# voeding.net
KiCad netlist of a schematic drawn in Altium Designer
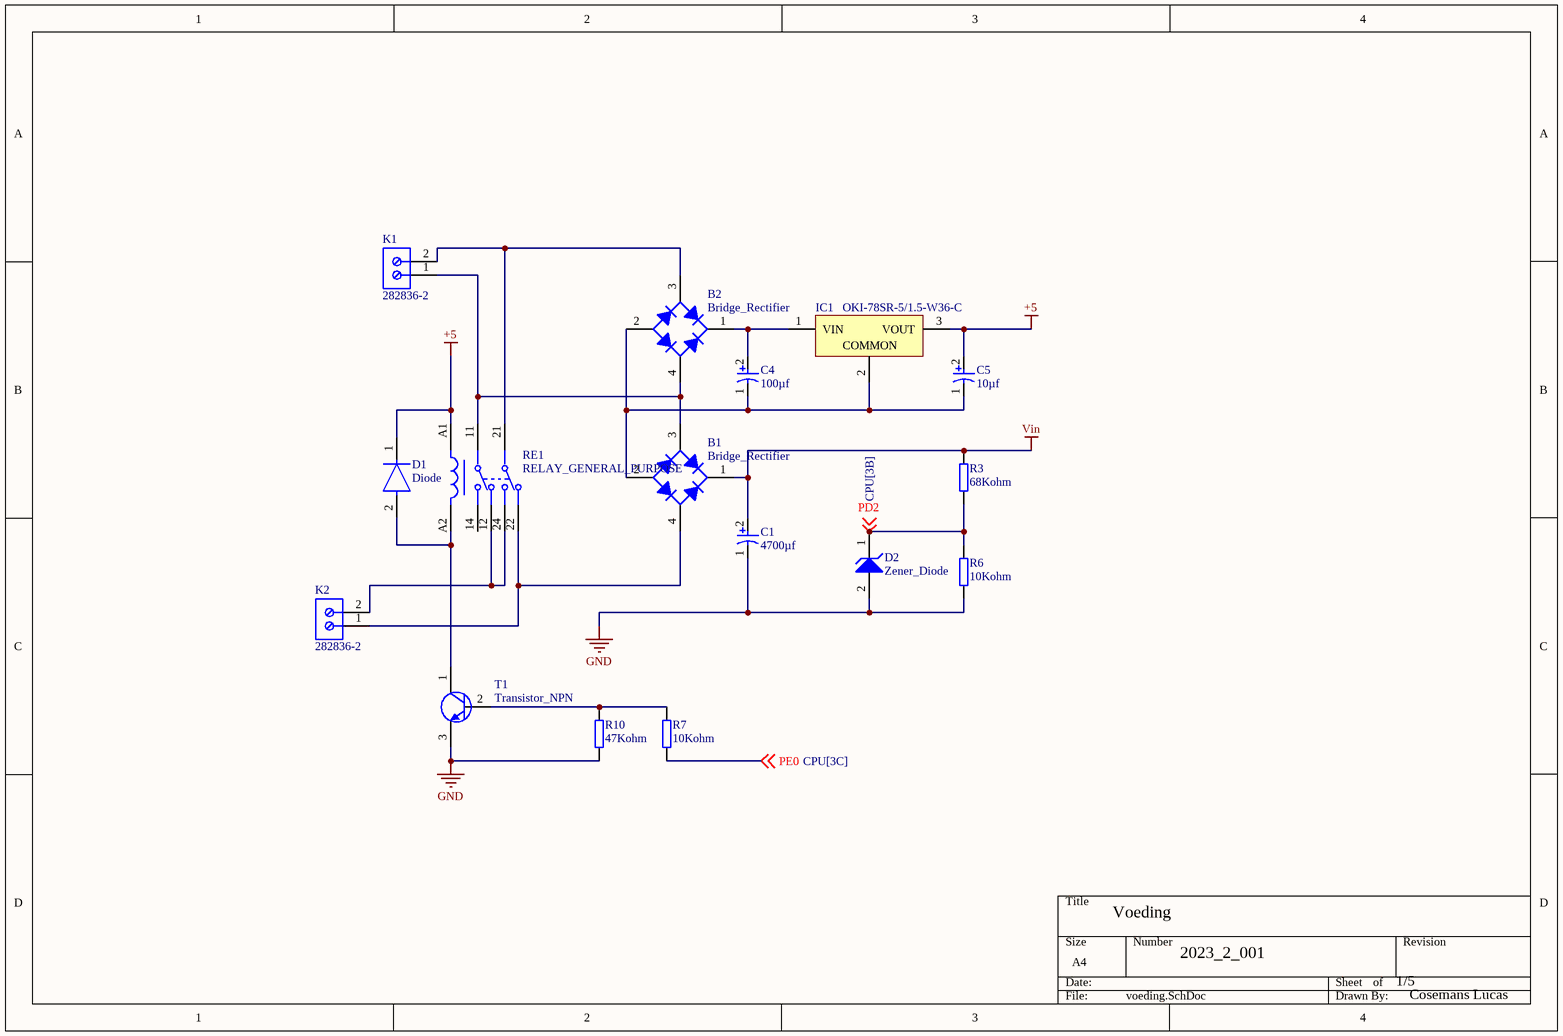
[diagram p0: voeding.SchDoc]

(export (version "E")
  (design (tool "Eeschema 10.0.6"))
  (components
    (comp (ref "B1")
      (value "Bridge_Rectifier")
      (footprint "ttf")
      (fields (field (name "MANUFACTURER") "Diodes Inc"))
      (libsource (lib "Schematic_soldeerstation") (part "Bridge_Rectifier"))
    )
    (comp (ref "B2")
      (value "Bridge_Rectifier")
      (footprint "ttf")
      (fields (field (name "MANUFACTURER") "Diodes Inc"))
      (libsource (lib "Schematic_soldeerstation") (part "Bridge_Rectifier"))
    )
    (comp (ref "C1")
      (value "4700µf")
      (footprint "CE_D25_L25_plugin")
      (fields (field (name "MANUFACTURER") "Panasonic"))
      (libsource (lib "Schematic_soldeerstation") (part "Capacitor_Electrolytic"))
    )
    (comp (ref "C4")
      (value "100µf")
      (footprint "CE_D6,3_L4,5")
      (fields (field (name "MANUFACTURER") "Panasonic"))
      (libsource (lib "Schematic_soldeerstation") (part "Capacitor_Electrolytic"))
    )
    (comp (ref "C5")
      (value "10µf")
      (footprint "CE_D6,3_L4,5")
      (fields (field (name "MANUFACTURER") "Panasonic"))
      (libsource (lib "Schematic_soldeerstation") (part "Capacitor_Electrolytic"))
    )
    (comp (ref "D1")
      (value "Diode")
      (footprint "SOD-123FL")
      (fields
        (field (name "MANUFACTURER PART NUMBER") "1N4007")
        (field (name "MANUFACTURER") "Diotec")
        (field (name "OCTOPART") "https://octopart.com/1n4007-diotec-4040411")
      )
      (libsource (lib "Schematic_soldeerstation") (part "Diode"))
    )
    (comp (ref "D2")
      (value "Zener_Diode")
      (footprint "SOD-123FL")
      (fields (field (name "MANUFACTURER") "On Semiconductor") (field (name "PARTNUMBER") "1SMB5920BT3G"))
      (libsource (lib "Schematic_soldeerstation") (part "Zener_Diode"))
    )
    (comp (ref "IC1")
      (value "OKI-78SR-5/1.5-W36-C")
      (footprint "OKI78SR515W36C")
      (description "Non-Isolated DC/DC Converter, 7.5 W, 7 to 36 V, 1.5 A, -40 to 85 degC, 3-Pin THD, RoHS")
      (fields (field (name "MANUFACTURER") "Murata"))
      (libsource (lib "Schematic_soldeerstation") (part "OKI-78SR-5/1.5-W36-C"))
    )
    (comp (ref "K1")
      (value "282836-2")
      (footprint "2x1 Schroef pin TECO-282836-2_V")
      (description "Female Header, Pitch 5 mm, 1 x 2 Position, Height 10 mm, Tail Length 3.5 mm, Rohs, Bulk")
      (fields (field (name "VOLTAGE") "300V") (field (name "MANUFACTURER") "TE Connectivity"))
      (libsource (lib "Schematic_soldeerstation") (part "2x1 schroef pin"))
    )
    (comp (ref "K2")
      (value "282836-2")
      (footprint "2x1 Schroef pin TECO-282836-2_V")
      (description "Female Header, Pitch 5 mm, 1 x 2 Position, Height 10 mm, Tail Length 3.5 mm, Rohs, Bulk")
      (fields (field (name "VOLTAGE") "300V") (field (name "MANUFACTURER") "TE Connectivity"))
      (libsource (lib "Schematic_soldeerstation") (part "2x1 schroef pin"))
    )
    (comp (ref "R3")
      (value "68Kohm")
      (footprint "R_0805_M")
      (fields (field (name "MANUFACTURER") "Vishay Dale") (field (name "PART NUMBER") "CRCW08050000Z0EA"))
      (libsource (lib "Schematic_soldeerstation") (part "Resistor"))
    )
    (comp (ref "R6")
      (value "10Kohm")
      (footprint "R_0805_M")
      (fields (field (name "MANUFACTURER") "Vishay Dale") (field (name "PART NUMBER") "CRCW08050000Z0EA"))
      (libsource (lib "Schematic_soldeerstation") (part "Resistor"))
    )
    (comp (ref "R7")
      (value "10Kohm")
      (footprint "R_0805_M")
      (fields (field (name "MANUFACTURER") "Vishay Dale") (field (name "PART NUMBER") "CRCW08050000Z0EA"))
      (libsource (lib "Schematic_soldeerstation") (part "Resistor"))
    )
    (comp (ref "R10")
      (value "47Kohm")
      (footprint "R_0805_M")
      (fields (field (name "MANUFACTURER") "Vishay Dale") (field (name "PART NUMBER") "CRCW08050000Z0EA"))
      (libsource (lib "Schematic_soldeerstation") (part "Resistor"))
    )
    (comp (ref "RE1")
      (value "RELAY_GENERAL_PURPOSE")
      (footprint "RT42")
      (fields
        (field (name "MANUFACTURER PART NUMBER") "RT424005")
        (field (name "OCTOPART") "https://octopart.com/5-1393243-9-te+connectivity-41835766")
        (field (name "MANUFACTURER") "TE Connectivity")
      )
      (libsource (lib "Schematic_soldeerstation") (part "RELAY_GENERAL_PURPOSE"))
    )
    (comp (ref "T1")
      (value "Transistor_NPN")
      (footprint "SOT_23")
      (fields (field (name "MANUFACTURER") "On Semiconductor") (field (name "PARTNUMBER") "BC547C"))
      (libsource (lib "Schematic_soldeerstation") (part "Transistor_NPN"))
    )
  )
  (nets
    (net (code "1") (name "+5") (class "Default")
      (node (ref "C5") (pin "2") (pinfunction "2_2") (pintype "passive"))
      (node (ref "D1") (pin "1") (pinfunction "C_1") (pintype "passive"))
      (node (ref "IC1") (pin "3") (pinfunction "VOUT_3") (pintype "power_in"))
      (node (ref "RE1") (pin "A1") (pinfunction "A1_A1") (pintype "passive"))
    )
    (net (code "2") (name "GND") (class "Default")
      (node (ref "C1") (pin "1") (pinfunction "1_1") (pintype "passive"))
      (node (ref "D2") (pin "2") (pinfunction "A_2") (pintype "passive"))
      (node (ref "R10") (pin "1") (pinfunction "1_1") (pintype "passive"))
      (node (ref "R6") (pin "1") (pinfunction "1_1") (pintype "passive"))
      (node (ref "T1") (pin "3") (pinfunction "E_3") (pintype "passive"))
    )
    (net (code "3") (name "Net-(B1-A)") (class "Default")
      (node (ref "B1") (pin "2") (pinfunction "A_2") (pintype "passive"))
      (node (ref "B2") (pin "2") (pinfunction "A_2") (pintype "passive"))
      (node (ref "C4") (pin "1") (pinfunction "1_1") (pintype "passive"))
      (node (ref "C5") (pin "1") (pinfunction "1_1") (pintype "passive"))
      (node (ref "IC1") (pin "2") (pinfunction "COMMON_2") (pintype "power_in"))
    )
    (net (code "4") (name "Net-(B1-C-Pad3)") (class "Default")
      (node (ref "B1") (pin "3") (pinfunction "C_3") (pintype "passive"))
      (node (ref "B2") (pin "4") (pinfunction "C_4") (pintype "passive"))
      (node (ref "K1") (pin "1") (pinfunction "1_1") (pintype "passive"))
      (node (ref "RE1") (pin "11") (pinfunction "11_11") (pintype "passive"))
    )
    (net (code "5") (name "Net-(B1-C-Pad4)") (class "Default")
      (node (ref "B1") (pin "4") (pinfunction "C_4") (pintype "passive"))
      (node (ref "K2") (pin "1") (pinfunction "1_1") (pintype "passive"))
      (node (ref "RE1") (pin "22") (pinfunction "22_22") (pintype "passive"))
    )
    (net (code "6") (name "Net-(B2-C-Pad3)") (class "Default")
      (node (ref "B2") (pin "3") (pinfunction "C_3") (pintype "passive"))
      (node (ref "K1") (pin "2") (pinfunction "2_2") (pintype "passive"))
      (node (ref "RE1") (pin "21") (pinfunction "21_21") (pintype "passive"))
    )
    (net (code "7") (name "Net-(B2-K)") (class "Default")
      (node (ref "B2") (pin "1") (pinfunction "K_1") (pintype "passive"))
      (node (ref "C4") (pin "2") (pinfunction "2_2") (pintype "passive"))
      (node (ref "IC1") (pin "1") (pinfunction "VIN_1") (pintype "power_in"))
    )
    (net (code "8") (name "Net-(D1-A)") (class "Default")
      (node (ref "D1") (pin "2") (pinfunction "A_2") (pintype "passive"))
      (node (ref "RE1") (pin "A2") (pinfunction "A2_A2") (pintype "passive"))
      (node (ref "T1") (pin "1") (pinfunction "C_1") (pintype "passive"))
    )
    (net (code "9") (name "Net-(K2-Pad2)") (class "Default")
      (node (ref "K2") (pin "2") (pinfunction "2_2") (pintype "passive"))
      (node (ref "RE1") (pin "12") (pinfunction "12_12") (pintype "passive"))
      (node (ref "RE1") (pin "24") (pinfunction "24_24") (pintype "passive"))
    )
    (net (code "10") (name "Net-(T1-B)") (class "Default")
      (node (ref "R10") (pin "2") (pinfunction "2_2") (pintype "passive"))
      (node (ref "R7") (pin "2") (pinfunction "2_2") (pintype "passive"))
      (node (ref "T1") (pin "2") (pinfunction "B_2") (pintype "passive"))
    )
    (net (code "11") (name "PD2") (class "Default")
      (node (ref "D2") (pin "1") (pinfunction "K_1") (pintype "passive"))
      (node (ref "R3") (pin "1") (pinfunction "1_1") (pintype "passive"))
      (node (ref "R6") (pin "2") (pinfunction "2_2") (pintype "passive"))
    )
    (net (code "12") (name "PE0") (class "Default")
      (node (ref "R7") (pin "1") (pinfunction "1_1") (pintype "passive"))
    )
    (net (code "13") (name "Vin") (class "Default")
      (node (ref "B1") (pin "1") (pinfunction "K_1") (pintype "passive"))
      (node (ref "C1") (pin "2") (pinfunction "2_2") (pintype "passive"))
      (node (ref "R3") (pin "2") (pinfunction "2_2") (pintype "passive"))
    )
    (net (code "14") (name "unconnected-(RE1-Pad14)") (class "Default")
      (node (ref "RE1") (pin "14") (pinfunction "14_14") (pintype "passive"))
    )
  )
)
